# max32625pico.net
KiCad netlist of a schematic drawn in EAGLE
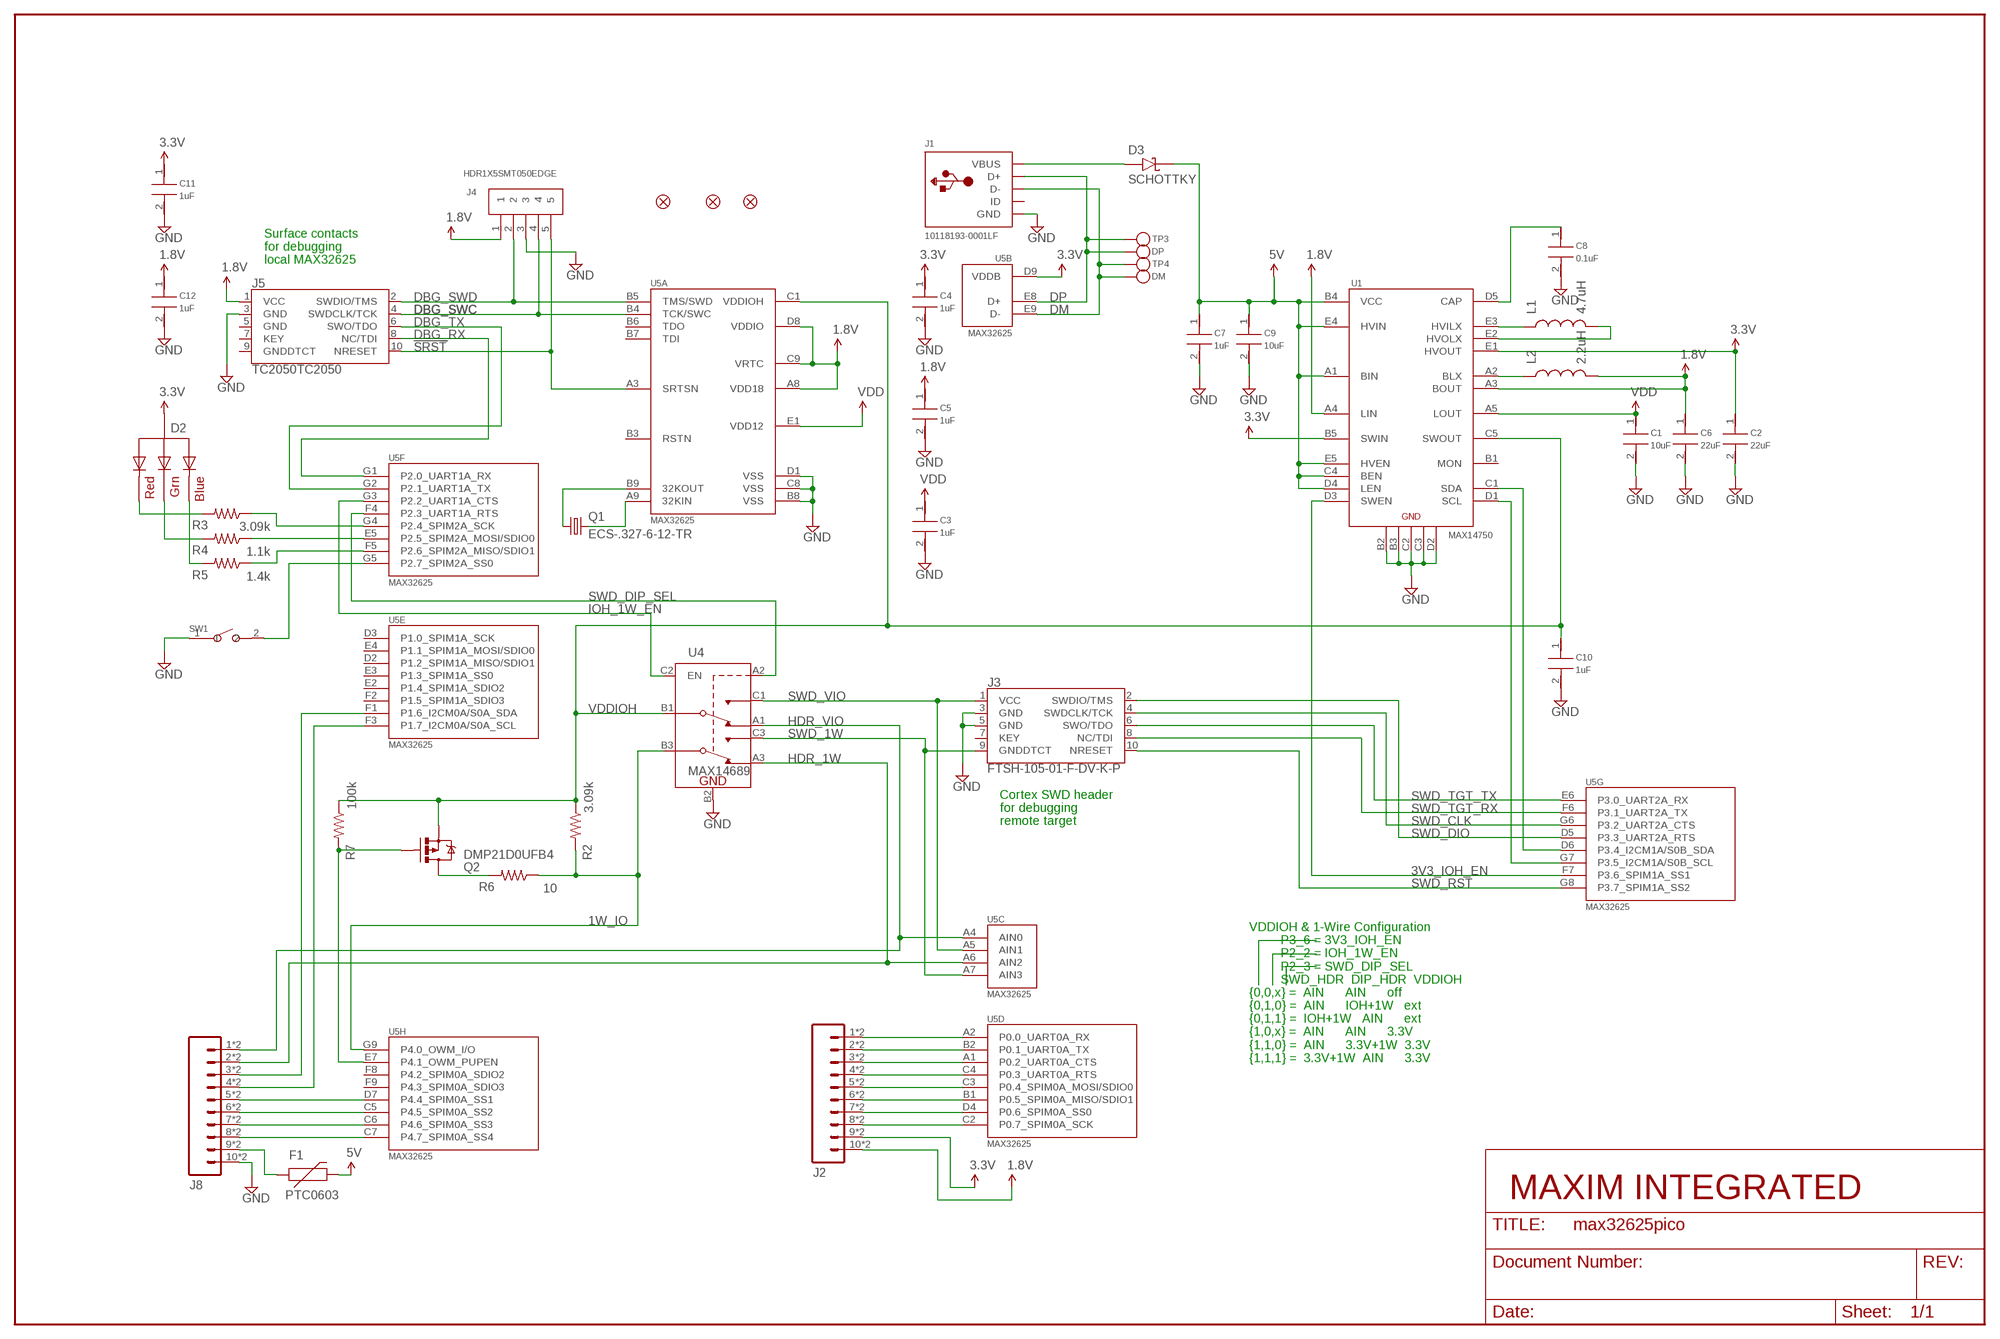
[diagram p0: schematic, sheet 1]

(export (version "E")
  (design (tool "Eeschema 10.0.6"))
  (components
    (comp (ref "C1")
      (value "10uF")
      (footprint "eagle-import:0402")
      (libsource (lib "eagle-import") (part "C"))
    )
    (comp (ref "C2")
      (value "22uF")
      (footprint "eagle-import:0402")
      (libsource (lib "eagle-import") (part "C"))
    )
    (comp (ref "C3")
      (value "1uF")
      (footprint "eagle-import:0402")
      (libsource (lib "eagle-import") (part "C"))
    )
    (comp (ref "C4")
      (value "1uF")
      (footprint "eagle-import:0402")
      (libsource (lib "eagle-import") (part "C"))
    )
    (comp (ref "C5")
      (value "1uF")
      (footprint "eagle-import:0402")
      (libsource (lib "eagle-import") (part "C"))
    )
    (comp (ref "C6")
      (value "22uF")
      (footprint "eagle-import:0402")
      (libsource (lib "eagle-import") (part "C"))
    )
    (comp (ref "C7")
      (value "1uF")
      (footprint "eagle-import:0402")
      (libsource (lib "eagle-import") (part "C"))
    )
    (comp (ref "C8")
      (value "0.1uF")
      (footprint "eagle-import:0402")
      (libsource (lib "eagle-import") (part "C"))
    )
    (comp (ref "C9")
      (value "10uF")
      (footprint "eagle-import:0402")
      (libsource (lib "eagle-import") (part "C"))
    )
    (comp (ref "C10")
      (value "1uF")
      (footprint "eagle-import:0402")
      (libsource (lib "eagle-import") (part "C"))
    )
    (comp (ref "C11")
      (value "1uF")
      (footprint "eagle-import:0402")
      (libsource (lib "eagle-import") (part "C"))
    )
    (comp (ref "C12")
      (value "1uF")
      (footprint "eagle-import:0402")
      (libsource (lib "eagle-import") (part "C"))
    )
    (comp (ref "D2")
      (value "RGBLED_CALUMIX-SML-LX0404")
      (footprint "eagle-import:LUMIX-SML-LX0404")
      (libsource (lib "eagle-import") (part "RGBLED_CALUMIX-SML-LX0404"))
    )
    (comp (ref "D3")
      (value "SCHOTTKY")
      (footprint "eagle-import:DCSP1006010-N1")
      (libsource (lib "eagle-import") (part "SCHOTTKY"))
    )
    (comp (ref "DM")
      (value "TESTPOINTROUND1.5MM")
      (footprint "eagle-import:TESTPOINT_ROUND_1.5MM")
      (libsource (lib "eagle-import") (part "TESTPOINTROUND1.5MM"))
    )
    (comp (ref "DP")
      (value "TESTPOINTROUND1.5MM")
      (footprint "eagle-import:TESTPOINT_ROUND_1.5MM")
      (libsource (lib "eagle-import") (part "TESTPOINTROUND1.5MM"))
    )
    (comp (ref "F1")
      (value "PTC0603")
      (footprint "eagle-import:0603")
      (libsource (lib "eagle-import") (part "PTC0603"))
    )
    (comp (ref "FD1")
      (value "FIDUCIALUFIDUCIAL")
      (footprint "eagle-import:MICRO-FIDUCIAL")
      (libsource (lib "eagle-import") (part "FIDUCIALUFIDUCIAL"))
    )
    (comp (ref "FD2")
      (value "FIDUCIALUFIDUCIAL")
      (footprint "eagle-import:MICRO-FIDUCIAL")
      (libsource (lib "eagle-import") (part "FIDUCIALUFIDUCIAL"))
    )
    (comp (ref "FD5")
      (value "FIDUCIALUFIDUCIAL")
      (footprint "eagle-import:MICRO-FIDUCIAL")
      (libsource (lib "eagle-import") (part "FIDUCIALUFIDUCIAL"))
    )
    (comp (ref "J1")
      (value "10118193-0001LF")
      (footprint "eagle-import:MICRO-USB5+6P-SMD-0.65-B")
      (libsource (lib "eagle-import") (part "MICRO-USB-SMD-B-(10118193-0001LF)"))
    )
    (comp (ref "J2")
      (value "M10SMT_L")
      (footprint "eagle-import:1X10_SMT_L")
      (libsource (lib "eagle-import") (part "M10SMT_L"))
    )
    (comp (ref "J3")
      (value "FTSH-105-01-F-DV-K-P")
      (footprint "eagle-import:SAMTECH_FTSH-105-01")
      (libsource (lib "eagle-import") (part "CORTEX_DEBUGSMD"))
    )
    (comp (ref "J4")
      (value "HDR1X5SMT050EDGE")
      (footprint "eagle-import:HDR_SMT_1X5_050_EDGE")
      (libsource (lib "eagle-import") (part "HDR1X5SMT050EDGE"))
    )
    (comp (ref "J5")
      (value "TC2050TC2050")
      (footprint "eagle-import:TC2050")
      (libsource (lib "eagle-import") (part "TC2050TC2050"))
    )
    (comp (ref "J8")
      (value "M10SMT_R")
      (footprint "eagle-import:1X10_SMT_R")
      (libsource (lib "eagle-import") (part "M10SMT_R"))
    )
    (comp (ref "L1")
      (value "4.7uH")
      (footprint "eagle-import:IND2016")
      (libsource (lib "eagle-import") (part "INDUCTOR2016"))
    )
    (comp (ref "L2")
      (value "2.2uH")
      (footprint "eagle-import:IND2016")
      (libsource (lib "eagle-import") (part "INDUCTOR2016"))
    )
    (comp (ref "Q1")
      (value "ECS-.327-6-12-TR")
      (footprint "eagle-import:FC-12M")
      (libsource (lib "eagle-import") (part "FC-12M"))
    )
    (comp (ref "Q2")
      (value "DMP21D0UFB4")
      (footprint "eagle-import:SOT-883")
      (libsource (lib "eagle-import") (part "PMZ600UNE"))
    )
    (comp (ref "R2")
      (value "3.09k")
      (footprint "eagle-import:0402")
      (libsource (lib "eagle-import") (part "R-US_0402"))
    )
    (comp (ref "R3")
      (value "3.09k")
      (footprint "eagle-import:0402")
      (libsource (lib "eagle-import") (part "R-US_0402"))
    )
    (comp (ref "R4")
      (value "1.1k")
      (footprint "eagle-import:0402")
      (libsource (lib "eagle-import") (part "R-US_0402"))
    )
    (comp (ref "R5")
      (value "1.4k")
      (footprint "eagle-import:0402")
      (libsource (lib "eagle-import") (part "R-US_0402"))
    )
    (comp (ref "R6")
      (value "10")
      (footprint "eagle-import:0402")
      (libsource (lib "eagle-import") (part "R-US_0402"))
    )
    (comp (ref "R7")
      (value "100k")
      (footprint "eagle-import:0402")
      (libsource (lib "eagle-import") (part "R-US_0402"))
    )
    (comp (ref "SW1")
      (value "SMD-BUTTON(2P-3.0X2.5X1.2+0.4MM)-B3U-1000P-2P-SMD")
      (footprint "eagle-import:SW2-2.6-3.0X2.5X1.2+0.4MM")
      (libsource (lib "eagle-import") (part "SMD-BUTTON(2P-3.0X2.5X1.2+0.4MM)-B3U-1000P-2P-SMD"))
    )
    (comp (ref "TP3")
      (value "TESTPOINTRECT25X50MIL")
      (footprint "eagle-import:TESTPOINT_RECT_25X50MIL")
      (libsource (lib "eagle-import") (part "TESTPOINTRECT25X50MIL"))
    )
    (comp (ref "TP4")
      (value "TESTPOINTRECT25X50MIL")
      (footprint "eagle-import:TESTPOINT_RECT_25X50MIL")
      (libsource (lib "eagle-import") (part "TESTPOINTRECT25X50MIL"))
    )
    (comp (ref "U$1")
      (value "MAXIM_LOGO")
      (footprint "eagle-import:MXM_LOGO_6MM")
      (libsource (lib "eagle-import") (part "MAXIM_LOGO"))
    )
    (comp (ref "U1")
      (value "MAX14750")
      (footprint "eagle-import:W252M2-1")
      (libsource (lib "eagle-import") (part "MAX14750"))
    )
    (comp (ref "U4")
      (value "MAX14689")
      (footprint "eagle-import:W91J1-1")
      (libsource (lib "eagle-import") (part "MAX14689"))
    )
    (comp (ref "U5")
      (value "MAX32625")
      (footprint "eagle-import:W633B3-1")
      (libsource (lib "eagle-import") (part "MAX32625"))
    )
  )
  (nets
    (net (code "1") (name "/1W_IO") (class "Default")
      (node (ref "R2") (pin "2") (pinfunction "2_2") (pintype "passive"))
      (node (ref "R6") (pin "1") (pinfunction "1_1") (pintype "passive"))
      (node (ref "U4") (pin "B3") (pinfunction "COM2_B3") (pintype "bidirectional"))
      (node (ref "U5") (pin "G9") (pinfunction "P4.0_OWM_I/O_G9") (pintype "bidirectional"))
    )
    (net (code "2") (name "/3V3_IOH_EN") (class "Default")
      (node (ref "U1") (pin "D3") (pinfunction "SWEN_D3") (pintype "input"))
      (node (ref "U5") (pin "F7") (pinfunction "P3.6_SPIM1A_SS1_F7") (pintype "bidirectional"))
    )
    (net (code "3") (name "/DBG_RX") (class "Default")
      (node (ref "J5") (pin "8") (pinfunction "NC/TDI_8") (pintype "bidirectional"))
      (node (ref "U5") (pin "G1") (pinfunction "P2.0_UART1A_RX_G1") (pintype "bidirectional"))
    )
    (net (code "4") (name "/DBG_SWC") (class "Default")
      (node (ref "J4") (pin "4") (pinfunction "4_4") (pintype "bidirectional"))
      (node (ref "J5") (pin "4") (pinfunction "SWDCLK/TCK_4") (pintype "bidirectional"))
      (node (ref "U5") (pin "B4") (pinfunction "TCK/SWC_B4") (pintype "input"))
    )
    (net (code "5") (name "/DBG_SWD") (class "Default")
      (node (ref "J4") (pin "2") (pinfunction "2_2") (pintype "bidirectional"))
      (node (ref "J5") (pin "2") (pinfunction "SWDIO/TMS_2") (pintype "bidirectional"))
      (node (ref "U5") (pin "B5") (pinfunction "TMS/SWD_B5") (pintype "bidirectional"))
    )
    (net (code "6") (name "/DBG_TX") (class "Default")
      (node (ref "J5") (pin "6") (pinfunction "SWO/TDO_6") (pintype "bidirectional"))
      (node (ref "U5") (pin "G2") (pinfunction "P2.1_UART1A_TX_G2") (pintype "bidirectional"))
    )
    (net (code "7") (name "/DM") (class "Default")
      (node (ref "DM") (pin "P$1") (pinfunction "P$1_P$1") (pintype "bidirectional"))
      (node (ref "J1") (pin "2") (pinfunction "D-_2") (pintype "bidirectional"))
      (node (ref "TP4") (pin "P$1") (pinfunction "P$1_P$1") (pintype "bidirectional"))
      (node (ref "U5") (pin "E9") (pinfunction "D-_E9") (pintype "bidirectional"))
    )
    (net (code "8") (name "/DP") (class "Default")
      (node (ref "DP") (pin "P$1") (pinfunction "P$1_P$1") (pintype "bidirectional"))
      (node (ref "J1") (pin "3") (pinfunction "D+_3") (pintype "bidirectional"))
      (node (ref "TP3") (pin "P$1") (pinfunction "P$1_P$1") (pintype "bidirectional"))
      (node (ref "U5") (pin "E8") (pinfunction "D+_E8") (pintype "bidirectional"))
    )
    (net (code "9") (name "/HDR_1W") (class "Default")
      (node (ref "J8") (pin "2") (pinfunction "2_2") (pintype "passive"))
      (node (ref "J8") (pin "S2") (pinfunction "2_S2") (pintype "passive"))
      (node (ref "U4") (pin "A3") (pinfunction "NC2_A3") (pintype "bidirectional"))
      (node (ref "U5") (pin "A6") (pinfunction "AIN2_A6") (pintype "input"))
    )
    (net (code "10") (name "/HDR_VIO") (class "Default")
      (node (ref "J8") (pin "1") (pinfunction "1_1") (pintype "passive"))
      (node (ref "J8") (pin "S1") (pinfunction "1_S1") (pintype "passive"))
      (node (ref "U4") (pin "A1") (pinfunction "NC1_A1") (pintype "bidirectional"))
      (node (ref "U5") (pin "A4") (pinfunction "AIN0_A4") (pintype "input"))
    )
    (net (code "11") (name "/IOH_1W_EN") (class "Default")
      (node (ref "U4") (pin "C2") (pinfunction "EN_C2") (pintype "bidirectional"))
      (node (ref "U5") (pin "G3") (pinfunction "P2.2_UART1A_CTS_G3") (pintype "bidirectional"))
    )
    (net (code "12") (name "/SWD_1W") (class "Default")
      (node (ref "J3") (pin "9") (pinfunction "GNDDTCT_9") (pintype "bidirectional"))
      (node (ref "U4") (pin "C3") (pinfunction "NO2_C3") (pintype "bidirectional"))
      (node (ref "U5") (pin "A7") (pinfunction "AIN3_A7") (pintype "input"))
    )
    (net (code "13") (name "/SWD_CLK") (class "Default")
      (node (ref "J3") (pin "4") (pinfunction "SWDCLK/TCK_4") (pintype "bidirectional"))
      (node (ref "U5") (pin "G6") (pinfunction "P3.2_UART2A_CTS_G6") (pintype "bidirectional"))
    )
    (net (code "14") (name "/SWD_DIO") (class "Default")
      (node (ref "J3") (pin "2") (pinfunction "SWDIO/TMS_2") (pintype "bidirectional"))
      (node (ref "U5") (pin "D5") (pinfunction "P3.3_UART2A_RTS_D5") (pintype "bidirectional"))
    )
    (net (code "15") (name "/SWD_DIP_SEL") (class "Default")
      (node (ref "U4") (pin "A2") (pinfunction "CB_A2") (pintype "input"))
      (node (ref "U5") (pin "F4") (pinfunction "P2.3_UART1A_RTS_F4") (pintype "bidirectional"))
    )
    (net (code "16") (name "/SWD_RST") (class "Default")
      (node (ref "J3") (pin "10") (pinfunction "NRESET_10") (pintype "bidirectional"))
      (node (ref "U5") (pin "G8") (pinfunction "P3.7_SPIM1A_SS2_G8") (pintype "bidirectional"))
    )
    (net (code "17") (name "/SWD_TGT_RX") (class "Default")
      (node (ref "J3") (pin "8") (pinfunction "NC/TDI_8") (pintype "bidirectional"))
      (node (ref "U5") (pin "F6") (pinfunction "P3.1_UART2A_TX_F6") (pintype "bidirectional"))
    )
    (net (code "18") (name "/SWD_TGT_TX") (class "Default")
      (node (ref "J3") (pin "6") (pinfunction "SWO/TDO_6") (pintype "bidirectional"))
      (node (ref "U5") (pin "E6") (pinfunction "P3.0_UART2A_RX_E6") (pintype "bidirectional"))
    )
    (net (code "19") (name "/SWD_VIO") (class "Default")
      (node (ref "J3") (pin "1") (pinfunction "VCC_1") (pintype "bidirectional"))
      (node (ref "U4") (pin "C1") (pinfunction "NO1_C1") (pintype "bidirectional"))
      (node (ref "U5") (pin "A5") (pinfunction "AIN1_A5") (pintype "input"))
    )
    (net (code "20") (name "/VDDIOH") (class "Default")
      (node (ref "C10") (pin "1") (pinfunction "1_1") (pintype "bidirectional"))
      (node (ref "Q2") (pin "2") (pinfunction "S_2") (pintype "passive"))
      (node (ref "R2") (pin "1") (pinfunction "1_1") (pintype "passive"))
      (node (ref "R7") (pin "1") (pinfunction "1_1") (pintype "passive"))
      (node (ref "U1") (pin "C5") (pinfunction "SWOUT_C5") (pintype "power_in"))
      (node (ref "U4") (pin "B1") (pinfunction "COM1_B1") (pintype "bidirectional"))
      (node (ref "U5") (pin "C1") (pinfunction "VDDIOH_C1") (pintype "power_in"))
    )
    (net (code "21") (name "/~{SRST}") (class "Default")
      (node (ref "J4") (pin "5") (pinfunction "5_5") (pintype "bidirectional"))
      (node (ref "J5") (pin "10") (pinfunction "NRESET_10") (pintype "bidirectional"))
      (node (ref "U5") (pin "A3") (pinfunction "SRTSN_A3") (pintype "bidirectional"))
    )
    (net (code "22") (name "1.8V") (class "Default")
      (node (ref "C12") (pin "1") (pinfunction "1_1") (pintype "bidirectional"))
      (node (ref "C5") (pin "1") (pinfunction "1_1") (pintype "bidirectional"))
      (node (ref "C6") (pin "1") (pinfunction "1_1") (pintype "bidirectional"))
      (node (ref "J2") (pin "10") (pinfunction "10_10") (pintype "passive"))
      (node (ref "J2") (pin "S10") (pinfunction "10_S10") (pintype "passive"))
      (node (ref "J4") (pin "1") (pinfunction "1_1") (pintype "bidirectional"))
      (node (ref "J5") (pin "1") (pinfunction "VCC_1") (pintype "bidirectional"))
      (node (ref "L2") (pin "2") (pinfunction "2_2") (pintype "passive"))
      (node (ref "U1") (pin "A3") (pinfunction "BOUT_A3") (pintype "input"))
      (node (ref "U1") (pin "A4") (pinfunction "LIN_A4") (pintype "power_in"))
      (node (ref "U5") (pin "A8") (pinfunction "VDD18_A8") (pintype "power_in"))
      (node (ref "U5") (pin "C9") (pinfunction "VRTC_C9") (pintype "power_in"))
      (node (ref "U5") (pin "D8") (pinfunction "VDDIO_D8") (pintype "power_in"))
    )
    (net (code "23") (name "3.3V") (class "Default")
      (node (ref "C11") (pin "1") (pinfunction "1_1") (pintype "bidirectional"))
      (node (ref "C2") (pin "1") (pinfunction "1_1") (pintype "bidirectional"))
      (node (ref "C4") (pin "1") (pinfunction "1_1") (pintype "bidirectional"))
      (node (ref "D2") (pin "1") (pinfunction "VCC_1") (pintype "bidirectional"))
      (node (ref "J2") (pin "9") (pinfunction "9_9") (pintype "passive"))
      (node (ref "J2") (pin "S9") (pinfunction "9_S9") (pintype "passive"))
      (node (ref "U1") (pin "B5") (pinfunction "SWIN_B5") (pintype "power_in"))
      (node (ref "U1") (pin "E1") (pinfunction "HVOUT_E1") (pintype "input"))
      (node (ref "U5") (pin "D9") (pinfunction "VDDB_D9") (pintype "power_in"))
    )
    (net (code "24") (name "5V") (class "Default")
      (node (ref "C7") (pin "1") (pinfunction "1_1") (pintype "bidirectional"))
      (node (ref "C9") (pin "1") (pinfunction "1_1") (pintype "bidirectional"))
      (node (ref "D3") (pin "1") (pinfunction "C_1") (pintype "passive"))
      (node (ref "F1") (pin "2") (pinfunction "2_2") (pintype "bidirectional"))
      (node (ref "U1") (pin "A1") (pinfunction "BIN_A1") (pintype "power_in"))
      (node (ref "U1") (pin "B4") (pinfunction "VCC_B4") (pintype "power_in"))
      (node (ref "U1") (pin "C4") (pinfunction "BEN_C4") (pintype "output"))
      (node (ref "U1") (pin "D4") (pinfunction "LEN_D4") (pintype "input"))
      (node (ref "U1") (pin "E4") (pinfunction "HVIN_E4") (pintype "power_in"))
      (node (ref "U1") (pin "E5") (pinfunction "HVEN_E5") (pintype "input"))
    )
    (net (code "25") (name "GND") (class "Default")
      (node (ref "C1") (pin "2") (pinfunction "2_2") (pintype "bidirectional"))
      (node (ref "C10") (pin "2") (pinfunction "2_2") (pintype "bidirectional"))
      (node (ref "C11") (pin "2") (pinfunction "2_2") (pintype "bidirectional"))
      (node (ref "C12") (pin "2") (pinfunction "2_2") (pintype "bidirectional"))
      (node (ref "C2") (pin "2") (pinfunction "2_2") (pintype "bidirectional"))
      (node (ref "C3") (pin "2") (pinfunction "2_2") (pintype "bidirectional"))
      (node (ref "C4") (pin "2") (pinfunction "2_2") (pintype "bidirectional"))
      (node (ref "C5") (pin "2") (pinfunction "2_2") (pintype "bidirectional"))
      (node (ref "C6") (pin "2") (pinfunction "2_2") (pintype "bidirectional"))
      (node (ref "C7") (pin "2") (pinfunction "2_2") (pintype "bidirectional"))
      (node (ref "C8") (pin "2") (pinfunction "2_2") (pintype "bidirectional"))
      (node (ref "C9") (pin "2") (pinfunction "2_2") (pintype "bidirectional"))
      (node (ref "J1") (pin "5") (pinfunction "GND_5") (pintype "power_in"))
      (node (ref "J1") (pin "S1") (pinfunction "GND_S1") (pintype "power_in"))
      (node (ref "J1") (pin "S2") (pinfunction "GND_S2") (pintype "power_in"))
      (node (ref "J1") (pin "S3") (pinfunction "GND_S3") (pintype "power_in"))
      (node (ref "J1") (pin "S4") (pinfunction "GND_S4") (pintype "power_in"))
      (node (ref "J1") (pin "S5") (pinfunction "GND_S5") (pintype "power_in"))
      (node (ref "J1") (pin "S6") (pinfunction "GND_S6") (pintype "power_in"))
      (node (ref "J3") (pin "3") (pinfunction "GND_3") (pintype "bidirectional"))
      (node (ref "J3") (pin "5") (pinfunction "GND_5") (pintype "bidirectional"))
      (node (ref "J4") (pin "3") (pinfunction "3_3") (pintype "bidirectional"))
      (node (ref "J5") (pin "3") (pinfunction "GND_3") (pintype "bidirectional"))
      (node (ref "J8") (pin "10") (pinfunction "10_10") (pintype "passive"))
      (node (ref "J8") (pin "S10") (pinfunction "10_S10") (pintype "passive"))
      (node (ref "SW1") (pin "1") (pinfunction "1_1") (pintype "bidirectional"))
      (node (ref "U1") (pin "B2") (pinfunction "GND_B2") (pintype "power_in"))
      (node (ref "U1") (pin "B3") (pinfunction "GND_B3") (pintype "power_in"))
      (node (ref "U1") (pin "C2") (pinfunction "GND_C2") (pintype "power_in"))
      (node (ref "U1") (pin "C3") (pinfunction "GND_C3") (pintype "power_in"))
      (node (ref "U1") (pin "D2") (pinfunction "GND_D2") (pintype "power_in"))
      (node (ref "U4") (pin "B2") (pinfunction "GND_B2") (pintype "bidirectional"))
      (node (ref "U5") (pin "B8") (pinfunction "VSS_B8") (pintype "power_in"))
      (node (ref "U5") (pin "C8") (pinfunction "VSS_C8") (pintype "power_in"))
      (node (ref "U5") (pin "D1") (pinfunction "VSS_D1") (pintype "power_in"))
    )
    (net (code "26") (name "Net-(D2-BLUE)") (class "Default")
      (node (ref "D2") (pin "3") (pinfunction "BLUE_3") (pintype "bidirectional"))
      (node (ref "R5") (pin "2") (pinfunction "2_2") (pintype "passive"))
    )
    (net (code "27") (name "Net-(D2-GREEN)") (class "Default")
      (node (ref "D2") (pin "4") (pinfunction "GREEN_4") (pintype "bidirectional"))
      (node (ref "R4") (pin "2") (pinfunction "2_2") (pintype "passive"))
    )
    (net (code "28") (name "Net-(D2-RED)") (class "Default")
      (node (ref "D2") (pin "2") (pinfunction "RED_2") (pintype "bidirectional"))
      (node (ref "R3") (pin "2") (pinfunction "2_2") (pintype "passive"))
    )
    (net (code "29") (name "Net-(D3-A)") (class "Default")
      (node (ref "D3") (pin "2") (pinfunction "A_2") (pintype "passive"))
      (node (ref "J1") (pin "1") (pinfunction "VBUS_1") (pintype "power_in"))
    )
    (net (code "30") (name "Net-(F1-Pad1)") (class "Default")
      (node (ref "F1") (pin "1") (pinfunction "1_1") (pintype "bidirectional"))
      (node (ref "J8") (pin "9") (pinfunction "9_9") (pintype "passive"))
      (node (ref "J8") (pin "S9") (pinfunction "9_S9") (pintype "passive"))
    )
    (net (code "31") (name "Net-(Q2-D)") (class "Default")
      (node (ref "Q2") (pin "3") (pinfunction "D_3") (pintype "passive"))
      (node (ref "R6") (pin "2") (pinfunction "2_2") (pintype "passive"))
    )
    (net (code "32") (name "Net-(Q2-G)") (class "Default")
      (node (ref "Q2") (pin "1") (pinfunction "G_1") (pintype "passive"))
      (node (ref "R7") (pin "2") (pinfunction "2_2") (pintype "passive"))
      (node (ref "U5") (pin "E7") (pinfunction "P4.1_OWM_PUPEN_E7") (pintype "bidirectional"))
    )
    (net (code "33") (name "Net-(U1-BLX)") (class "Default")
      (node (ref "L2") (pin "1") (pinfunction "1_1") (pintype "passive"))
      (node (ref "U1") (pin "A2") (pinfunction "BLX_A2") (pintype "power_in"))
    )
    (net (code "34") (name "Net-(U1-CAP)") (class "Default")
      (node (ref "C8") (pin "1") (pinfunction "1_1") (pintype "bidirectional"))
      (node (ref "U1") (pin "D5") (pinfunction "CAP_D5") (pintype "power_in"))
    )
    (net (code "35") (name "Net-(U1-HVILX)") (class "Default")
      (node (ref "L1") (pin "1") (pinfunction "1_1") (pintype "passive"))
      (node (ref "U1") (pin "E3") (pinfunction "HVILX_E3") (pintype "power_in"))
    )
    (net (code "36") (name "Net-(U1-HVOLX)") (class "Default")
      (node (ref "L1") (pin "2") (pinfunction "2_2") (pintype "passive"))
      (node (ref "U1") (pin "E2") (pinfunction "HVOLX_E2") (pintype "power_in"))
    )
    (net (code "37") (name "Net-(U1-SCL)") (class "Default")
      (node (ref "U1") (pin "D1") (pinfunction "SCL_D1") (pintype "input"))
      (node (ref "U5") (pin "G7") (pinfunction "P3.5_I2CM1A/S0B_SCL_G7") (pintype "bidirectional"))
    )
    (net (code "38") (name "Net-(U1-SDA)") (class "Default")
      (node (ref "U1") (pin "C1") (pinfunction "SDA_C1") (pintype "bidirectional"))
      (node (ref "U5") (pin "D6") (pinfunction "P3.4_I2CM1A/S0B_SDA_D6") (pintype "bidirectional"))
    )
    (net (code "39") (name "Net-(U5A-32KIN)") (class "Default")
      (node (ref "Q1") (pin "2") (pinfunction "2_2") (pintype "passive"))
      (node (ref "U5") (pin "A9") (pinfunction "32KIN_A9") (pintype "input"))
    )
    (net (code "40") (name "Net-(U5A-32KOUT)") (class "Default")
      (node (ref "Q1") (pin "1") (pinfunction "1_1") (pintype "passive"))
      (node (ref "U5") (pin "B9") (pinfunction "32KOUT_B9") (pintype "output"))
    )
    (net (code "41") (name "Net-(U5D-P0.0_UART0A_RX)") (class "Default")
      (node (ref "J2") (pin "1") (pinfunction "1_1") (pintype "passive"))
      (node (ref "J2") (pin "S1") (pinfunction "1_S1") (pintype "passive"))
      (node (ref "U5") (pin "A2") (pinfunction "P0.0_UART0A_RX_A2") (pintype "bidirectional"))
    )
    (net (code "42") (name "Net-(U5D-P0.1_UART0A_TX)") (class "Default")
      (node (ref "J2") (pin "2") (pinfunction "2_2") (pintype "passive"))
      (node (ref "J2") (pin "S2") (pinfunction "2_S2") (pintype "passive"))
      (node (ref "U5") (pin "B2") (pinfunction "P0.1_UART0A_TX_B2") (pintype "bidirectional"))
    )
    (net (code "43") (name "Net-(U5D-P0.2_UART0A_CTS)") (class "Default")
      (node (ref "J2") (pin "3") (pinfunction "3_3") (pintype "passive"))
      (node (ref "J2") (pin "S3") (pinfunction "3_S3") (pintype "passive"))
      (node (ref "U5") (pin "A1") (pinfunction "P0.2_UART0A_CTS_A1") (pintype "bidirectional"))
    )
    (net (code "44") (name "Net-(U5D-P0.3_UART0A_RTS)") (class "Default")
      (node (ref "J2") (pin "4") (pinfunction "4_4") (pintype "passive"))
      (node (ref "J2") (pin "S4") (pinfunction "4_S4") (pintype "passive"))
      (node (ref "U5") (pin "C4") (pinfunction "P0.3_UART0A_RTS_C4") (pintype "bidirectional"))
    )
    (net (code "45") (name "Net-(U5D-P0.4_SPIM0A_MOSI{slash}SDIO0)") (class "Default")
      (node (ref "J2") (pin "5") (pinfunction "5_5") (pintype "passive"))
      (node (ref "J2") (pin "S5") (pinfunction "5_S5") (pintype "passive"))
      (node (ref "U5") (pin "C3") (pinfunction "P0.4_SPIM0A_MOSI/SDIO0_C3") (pintype "bidirectional"))
    )
    (net (code "46") (name "Net-(U5D-P0.5_SPIM0A_MISO{slash}SDIO1)") (class "Default")
      (node (ref "J2") (pin "6") (pinfunction "6_6") (pintype "passive"))
      (node (ref "J2") (pin "S6") (pinfunction "6_S6") (pintype "passive"))
      (node (ref "U5") (pin "B1") (pinfunction "P0.5_SPIM0A_MISO/SDIO1_B1") (pintype "bidirectional"))
    )
    (net (code "47") (name "Net-(U5D-P0.6_SPIM0A_SS0)") (class "Default")
      (node (ref "J2") (pin "7") (pinfunction "7_7") (pintype "passive"))
      (node (ref "J2") (pin "S7") (pinfunction "7_S7") (pintype "passive"))
      (node (ref "U5") (pin "D4") (pinfunction "P0.6_SPIM0A_SS0_D4") (pintype "bidirectional"))
    )
    (net (code "48") (name "Net-(U5D-P0.7_SPIM0A_SCK)") (class "Default")
      (node (ref "J2") (pin "8") (pinfunction "8_8") (pintype "passive"))
      (node (ref "J2") (pin "S8") (pinfunction "8_S8") (pintype "passive"))
      (node (ref "U5") (pin "C2") (pinfunction "P0.7_SPIM0A_SCK_C2") (pintype "bidirectional"))
    )
    (net (code "49") (name "Net-(U5E-P1.6_I2CM0A{slash}S0A_SDA)") (class "Default")
      (node (ref "J8") (pin "3") (pinfunction "3_3") (pintype "passive"))
      (node (ref "J8") (pin "S3") (pinfunction "3_S3") (pintype "passive"))
      (node (ref "U5") (pin "F1") (pinfunction "P1.6_I2CM0A/S0A_SDA_F1") (pintype "bidirectional"))
    )
    (net (code "50") (name "Net-(U5E-P1.7_I2CM0A{slash}S0A_SCL)") (class "Default")
      (node (ref "J8") (pin "4") (pinfunction "4_4") (pintype "passive"))
      (node (ref "J8") (pin "S4") (pinfunction "4_S4") (pintype "passive"))
      (node (ref "U5") (pin "F3") (pinfunction "P1.7_I2CM0A/S0A_SCL_F3") (pintype "bidirectional"))
    )
    (net (code "51") (name "Net-(U5F-P2.4_SPIM2A_SCK)") (class "Default")
      (node (ref "R3") (pin "1") (pinfunction "1_1") (pintype "passive"))
      (node (ref "U5") (pin "G4") (pinfunction "P2.4_SPIM2A_SCK_G4") (pintype "bidirectional"))
    )
    (net (code "52") (name "Net-(U5F-P2.5_SPIM2A_MOSI{slash}SDIO0)") (class "Default")
      (node (ref "R4") (pin "1") (pinfunction "1_1") (pintype "passive"))
      (node (ref "U5") (pin "E5") (pinfunction "P2.5_SPIM2A_MOSI/SDIO0_E5") (pintype "bidirectional"))
    )
    (net (code "53") (name "Net-(U5F-P2.6_SPIM2A_MISO{slash}SDIO1)") (class "Default")
      (node (ref "R5") (pin "1") (pinfunction "1_1") (pintype "passive"))
      (node (ref "U5") (pin "F5") (pinfunction "P2.6_SPIM2A_MISO/SDIO1_F5") (pintype "bidirectional"))
    )
    (net (code "54") (name "Net-(U5F-P2.7_SPIM2A_SS0)") (class "Default")
      (node (ref "SW1") (pin "2") (pinfunction "2_2") (pintype "bidirectional"))
      (node (ref "U5") (pin "G5") (pinfunction "P2.7_SPIM2A_SS0_G5") (pintype "bidirectional"))
    )
    (net (code "55") (name "Net-(U5H-P4.4_SPIM0A_SS1)") (class "Default")
      (node (ref "J8") (pin "5") (pinfunction "5_5") (pintype "passive"))
      (node (ref "J8") (pin "S5") (pinfunction "5_S5") (pintype "passive"))
      (node (ref "U5") (pin "D7") (pinfunction "P4.4_SPIM0A_SS1_D7") (pintype "bidirectional"))
    )
    (net (code "56") (name "Net-(U5H-P4.5_SPIM0A_SS2)") (class "Default")
      (node (ref "J8") (pin "6") (pinfunction "6_6") (pintype "passive"))
      (node (ref "J8") (pin "S6") (pinfunction "6_S6") (pintype "passive"))
      (node (ref "U5") (pin "C5") (pinfunction "P4.5_SPIM0A_SS2_C5") (pintype "bidirectional"))
    )
    (net (code "57") (name "Net-(U5H-P4.6_SPIM0A_SS3)") (class "Default")
      (node (ref "J8") (pin "7") (pinfunction "7_7") (pintype "passive"))
      (node (ref "J8") (pin "S7") (pinfunction "7_S7") (pintype "passive"))
      (node (ref "U5") (pin "C6") (pinfunction "P4.6_SPIM0A_SS3_C6") (pintype "bidirectional"))
    )
    (net (code "58") (name "Net-(U5H-P4.7_SPIM0A_SS4)") (class "Default")
      (node (ref "J8") (pin "8") (pinfunction "8_8") (pintype "passive"))
      (node (ref "J8") (pin "S8") (pinfunction "8_S8") (pintype "passive"))
      (node (ref "U5") (pin "C7") (pinfunction "P4.7_SPIM0A_SS4_C7") (pintype "bidirectional"))
    )
    (net (code "59") (name "VDD") (class "Default")
      (node (ref "C1") (pin "1") (pinfunction "1_1") (pintype "bidirectional"))
      (node (ref "C3") (pin "1") (pinfunction "1_1") (pintype "bidirectional"))
      (node (ref "U1") (pin "A5") (pinfunction "LOUT_A5") (pintype "power_in"))
      (node (ref "U5") (pin "E1") (pinfunction "VDD12_E1") (pintype "power_in"))
    )
    (net (code "60") (name "unconnected-(J1-ID-Pad4)") (class "Default")
      (node (ref "J1") (pin "4") (pinfunction "ID_4") (pintype "bidirectional"))
    )
    (net (code "61") (name "unconnected-(J3-KEY-Pad7)") (class "Default")
      (node (ref "J3") (pin "7") (pinfunction "KEY_7") (pintype "bidirectional"))
    )
    (net (code "62") (name "unconnected-(J5-GND-Pad5)") (class "Default")
      (node (ref "J5") (pin "5") (pinfunction "GND_5") (pintype "bidirectional"))
    )
    (net (code "63") (name "unconnected-(J5-GNDDTCT-Pad9)") (class "Default")
      (node (ref "J5") (pin "9") (pinfunction "GNDDTCT_9") (pintype "bidirectional"))
    )
    (net (code "64") (name "unconnected-(J5-KEY-Pad7)") (class "Default")
      (node (ref "J5") (pin "7") (pinfunction "KEY_7") (pintype "bidirectional"))
    )
    (net (code "65") (name "unconnected-(U1-MON-PadB1)") (class "Default")
      (node (ref "U1") (pin "B1") (pinfunction "MON_B1") (pintype "bidirectional"))
    )
    (net (code "66") (name "unconnected-(U5A-RSTN-PadB3)") (class "Default")
      (node (ref "U5") (pin "B3") (pinfunction "RSTN_B3") (pintype "input"))
    )
    (net (code "67") (name "unconnected-(U5A-TDI-PadB7)") (class "Default")
      (node (ref "U5") (pin "B7") (pinfunction "TDI_B7") (pintype "input"))
    )
    (net (code "68") (name "unconnected-(U5A-TDO-PadB6)") (class "Default")
      (node (ref "U5") (pin "B6") (pinfunction "TDO_B6") (pintype "output"))
    )
    (net (code "69") (name "unconnected-(U5E-P1.0_SPIM1A_SCK-PadD3)") (class "Default")
      (node (ref "U5") (pin "D3") (pinfunction "P1.0_SPIM1A_SCK_D3") (pintype "bidirectional"))
    )
    (net (code "70") (name "unconnected-(U5E-P1.1_SPIM1A_MOSI{slash}SDIO0-PadE4)") (class "Default")
      (node (ref "U5") (pin "E4") (pinfunction "P1.1_SPIM1A_MOSI/SDIO0_E4") (pintype "bidirectional"))
    )
    (net (code "71") (name "unconnected-(U5E-P1.2_SPIM1A_MISO{slash}SDIO1-PadD2)") (class "Default")
      (node (ref "U5") (pin "D2") (pinfunction "P1.2_SPIM1A_MISO/SDIO1_D2") (pintype "bidirectional"))
    )
    (net (code "72") (name "unconnected-(U5E-P1.3_SPIM1A_SS0-PadE3)") (class "Default")
      (node (ref "U5") (pin "E3") (pinfunction "P1.3_SPIM1A_SS0_E3") (pintype "bidirectional"))
    )
    (net (code "73") (name "unconnected-(U5E-P1.4_SPIM1A_SDIO2-PadE2)") (class "Default")
      (node (ref "U5") (pin "E2") (pinfunction "P1.4_SPIM1A_SDIO2_E2") (pintype "bidirectional"))
    )
    (net (code "74") (name "unconnected-(U5E-P1.5_SPIM1A_SDIO3-PadF2)") (class "Default")
      (node (ref "U5") (pin "F2") (pinfunction "P1.5_SPIM1A_SDIO3_F2") (pintype "bidirectional"))
    )
    (net (code "75") (name "unconnected-(U5H-P4.2_SPIM0A_SDIO2-PadF8)") (class "Default")
      (node (ref "U5") (pin "F8") (pinfunction "P4.2_SPIM0A_SDIO2_F8") (pintype "bidirectional"))
    )
    (net (code "76") (name "unconnected-(U5H-P4.3_SPIM0A_SDIO3-PadF9)") (class "Default")
      (node (ref "U5") (pin "F9") (pinfunction "P4.3_SPIM0A_SDIO3_F9") (pintype "bidirectional"))
    )
  )
)
